# MinieasySens-RFM_V03-Build004.net
KiCad netlist of a schematic drawn in EAGLE
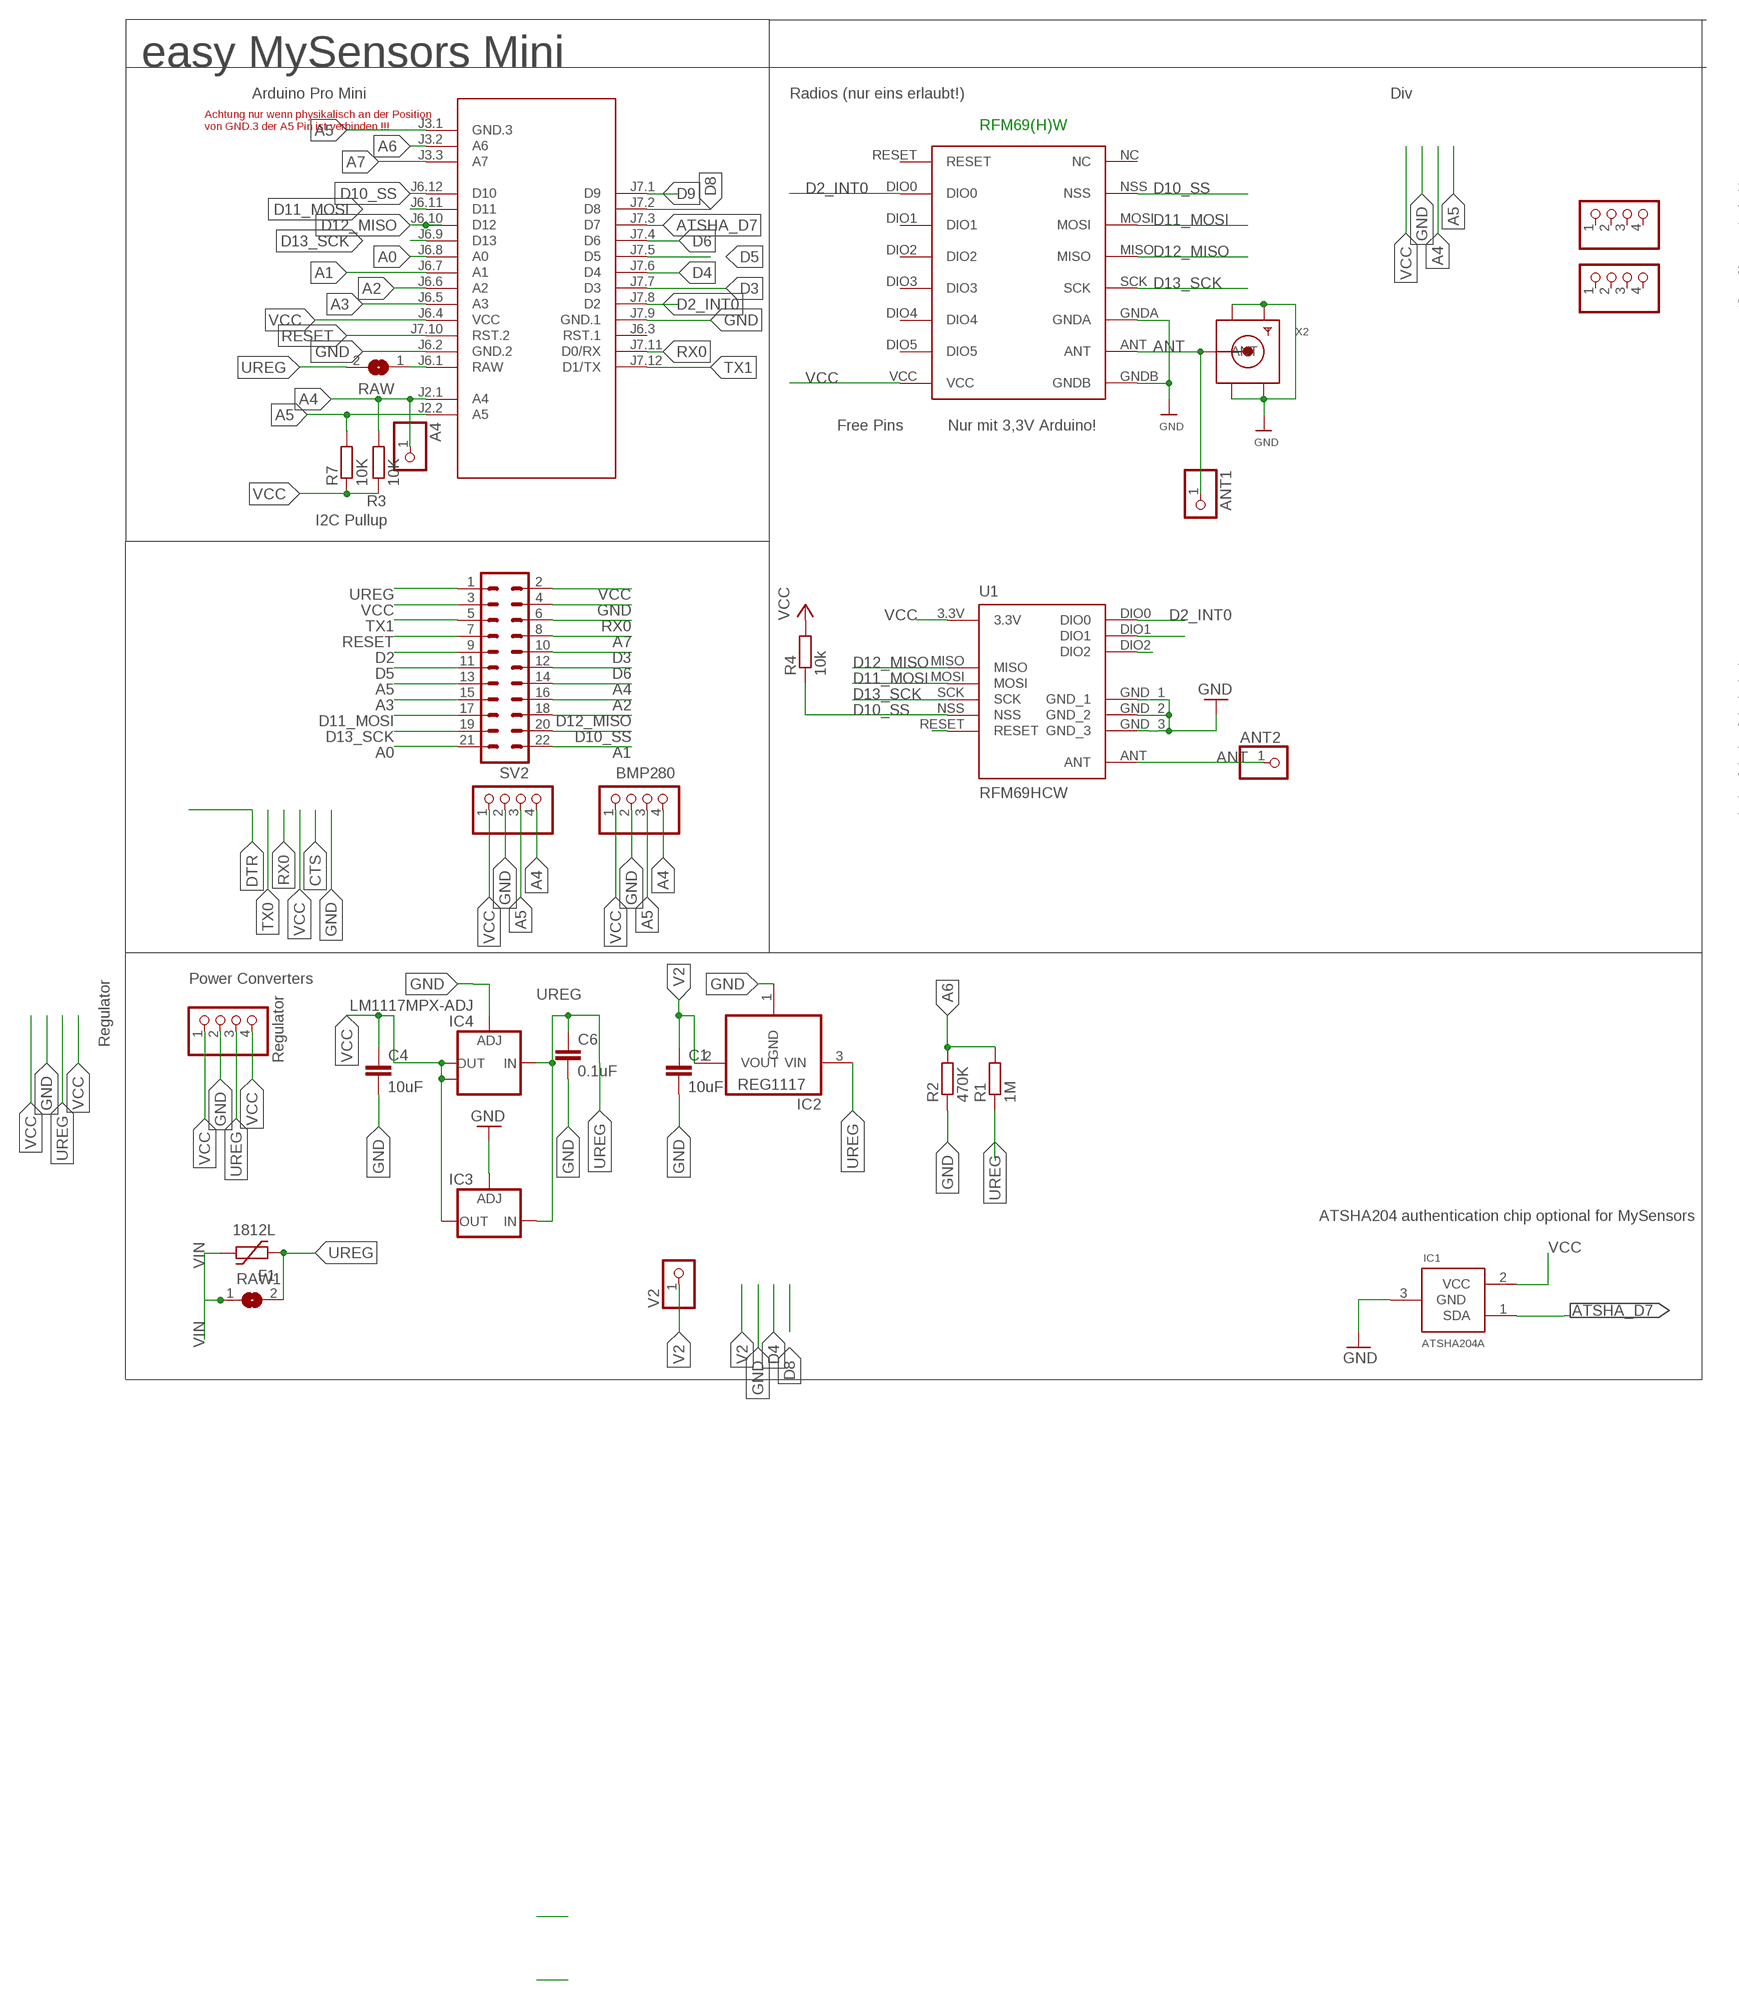
[diagram p0: schematic, sheet 1, part 1 of 2]
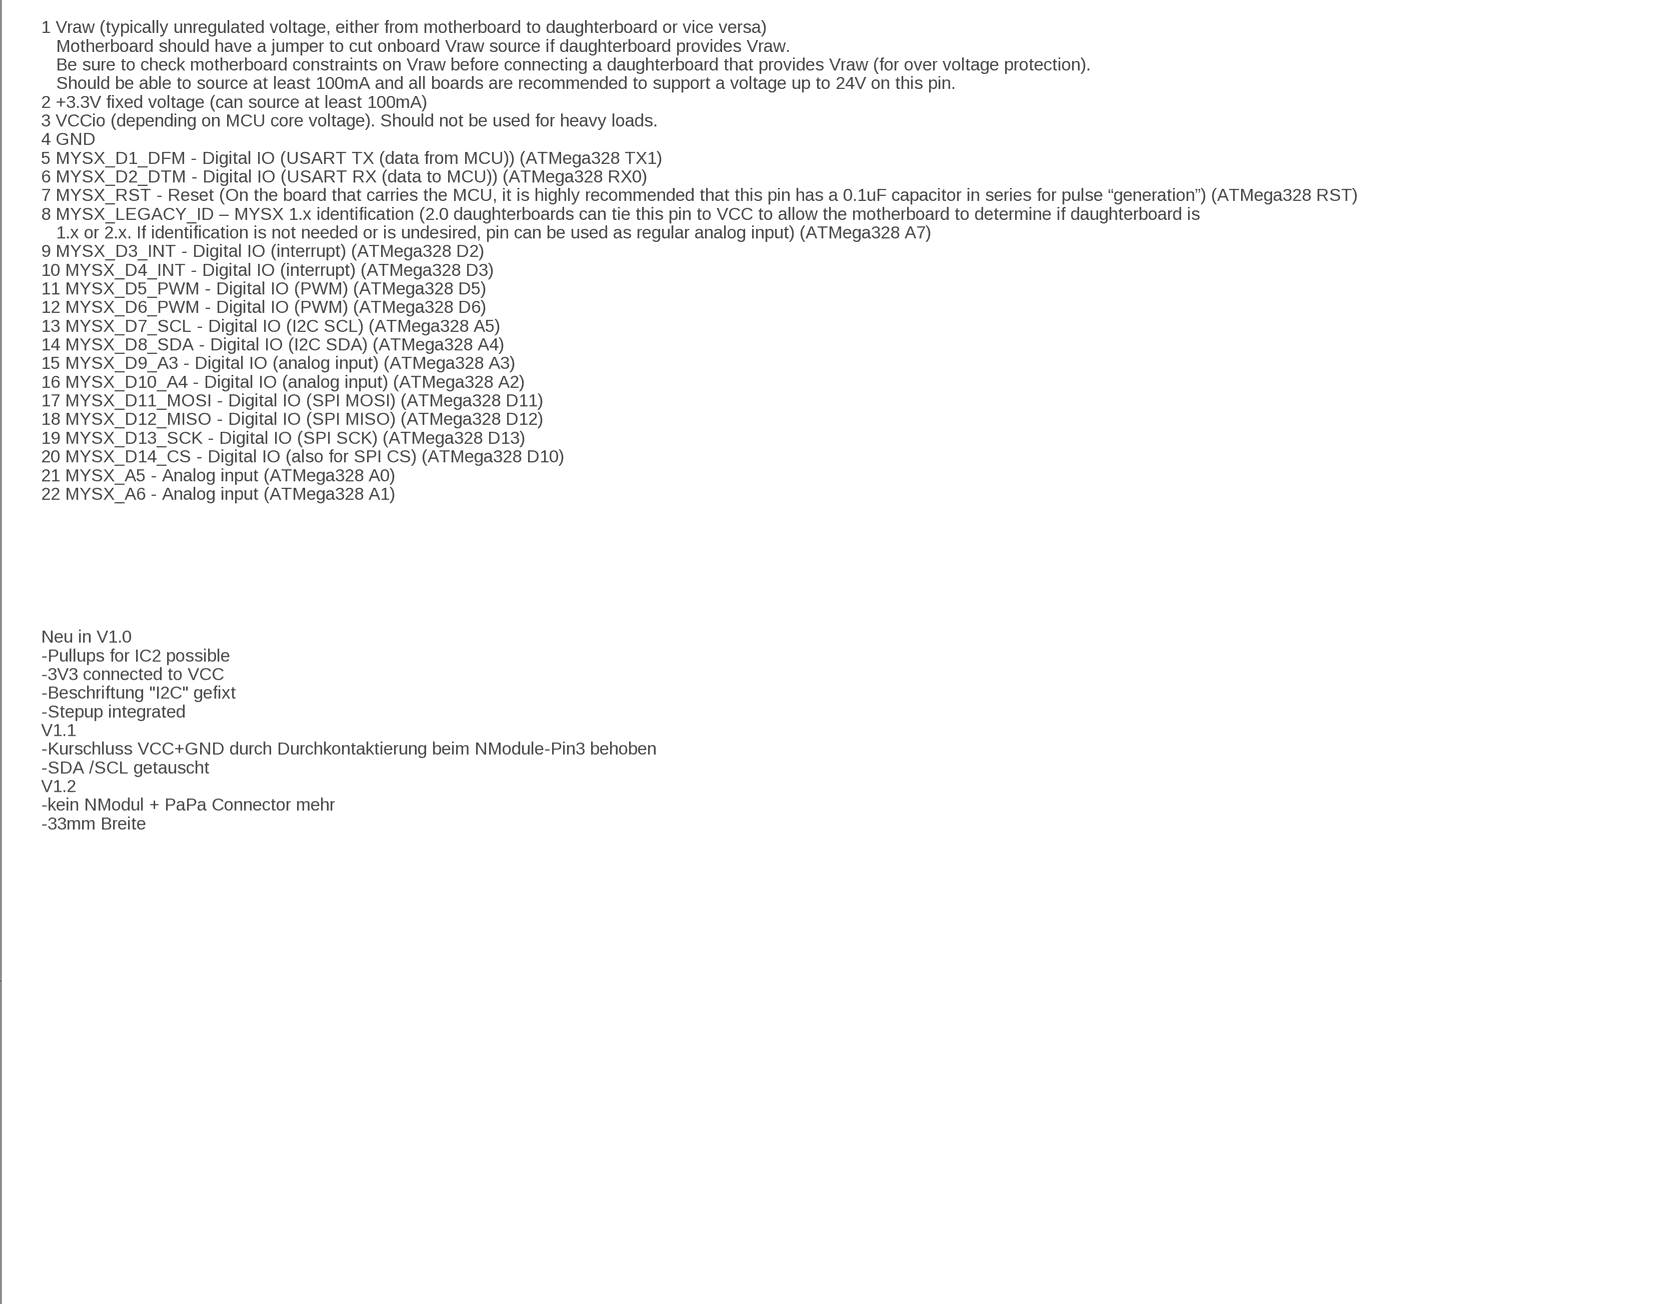
[diagram p1: schematic, sheet 1, part 2 of 2]

(export (version "E")
  (design (tool "Eeschema 10.0.6"))
  (components
    (comp (ref "A4")
      (value "PINHD-1X1")
      (footprint "eagle-import:1X01")
      (libsource (lib "eagle-import") (part "PINHD-1X1"))
    )
    (comp (ref "ANT1")
      (value "PINHD-1X1")
      (footprint "eagle-import:1X01")
      (libsource (lib "eagle-import") (part "PINHD-1X1"))
    )
    (comp (ref "ANT2")
      (value "PINHD-1X1")
      (footprint "eagle-import:1X01")
      (libsource (lib "eagle-import") (part "PINHD-1X1"))
    )
    (comp (ref "BH1750")
      (value "PINHD-1X04_2.54-S")
      (footprint "eagle-import:1X04-S")
      (libsource (lib "eagle-import") (part "PINHD-1X04_2.54-S"))
    )
    (comp (ref "C1")
      (value "10uF")
      (footprint "eagle-import:C1210")
      (libsource (lib "eagle-import") (part "C-EUC1210"))
    )
    (comp (ref "C4")
      (value "10uF")
      (footprint "eagle-import:C1210")
      (libsource (lib "eagle-import") (part "C-EUC1210"))
    )
    (comp (ref "C6")
      (value "0.1uF")
      (footprint "eagle-import:C1206")
      (libsource (lib "eagle-import") (part "C-EUC1206"))
    )
    (comp (ref "F1")
      (value "1812L")
      (footprint "eagle-import:1812L")
      (libsource (lib "eagle-import") (part "1812L"))
    )
    (comp (ref "I2C-1")
      (value "PINHD-1X04_2.54-S")
      (footprint "eagle-import:1X04-S")
      (libsource (lib "eagle-import") (part "PINHD-1X04_2.54-S"))
    )
    (comp (ref "IC1")
      (value "ATSHA204A")
      (footprint "eagle-import:SOT23")
      (libsource (lib "eagle-import") (part "ATSHA204A"))
    )
    (comp (ref "IC2")
      (value "REG1117")
      (footprint "eagle-import:SOT223")
      (libsource (lib "eagle-import") (part "REG1117"))
    )
    (comp (ref "IC3")
      (value "LD117ADT50TR")
      (footprint "eagle-import:DPACK")
      (libsource (lib "eagle-import") (part "LD117A?DT50TR"))
    )
    (comp (ref "IC4")
      (value "LM1117MPX-ADJ")
      (footprint "eagle-import:SOT223")
      (libsource (lib "eagle-import") (part "LM1117MPX-ADJ"))
    )
    (comp (ref "JP1")
      (value "PINHD-1X04_2.54-S")
      (footprint "eagle-import:1X04-S")
      (libsource (lib "eagle-import") (part "PINHD-1X04_2.54-S"))
    )
    (comp (ref "JP2")
      (value "PINHD-1X04_2.54-S")
      (footprint "eagle-import:1X04-S")
      (libsource (lib "eagle-import") (part "PINHD-1X04_2.54-S"))
    )
    (comp (ref "M1")
      (value "ARDUINO-PRO-MINI-3.3V#NP")
      (footprint "eagle-import:ARDUINO-PRO-MINI#NP")
      (libsource (lib "eagle-import") (part "ARDUINO-PRO-MINI-#NP3.3V"))
    )
    (comp (ref "R1")
      (value "1M")
      (footprint "eagle-import:R0805")
      (libsource (lib "eagle-import") (part "R-EU_R0805"))
    )
    (comp (ref "R2")
      (value "470K")
      (footprint "eagle-import:R0805")
      (libsource (lib "eagle-import") (part "R-EU_R0805"))
    )
    (comp (ref "R3")
      (value "10K")
      (footprint "eagle-import:R0805")
      (libsource (lib "eagle-import") (part "R-EU_R0805"))
    )
    (comp (ref "R4")
      (value "10k")
      (footprint "eagle-import:M0805")
      (libsource (lib "eagle-import") (part "R-EU_M0805"))
    )
    (comp (ref "R7")
      (value "10K")
      (footprint "eagle-import:R0805")
      (libsource (lib "eagle-import") (part "R-EU_R0805"))
    )
    (comp (ref "RAW") (value "SJ") (footprint "eagle-import:SJ") (libsource (lib "eagle-import") (part "SJ")))
    (comp (ref "RAW1")
      (value "SJ")
      (footprint "eagle-import:SJ")
      (libsource (lib "eagle-import") (part "SJ"))
    )
    (comp (ref "RFM69W")
      (value "RFM69HW")
      (footprint "eagle-import:RFM")
      (libsource (lib "eagle-import") (part "RFM69HW"))
    )
    (comp (ref "STEPDWN")
      (value "PINHD-1X04_2.54-S")
      (footprint "eagle-import:1X04-S")
      (libsource (lib "eagle-import") (part "PINHD-1X04_2.54-S"))
    )
    (comp (ref "SV2")
      (value "MA11-2")
      (footprint "eagle-import:MA11-2")
      (libsource (lib "eagle-import") (part "MA11-2"))
    )
    (comp (ref "U1")
      (value "RFM69HCW")
      (footprint "eagle-import:RFM69HCW-XXXS2")
      (libsource (lib "eagle-import") (part "RFM69HCW"))
    )
    (comp (ref "V2")
      (value "PINHD-1X1")
      (footprint "eagle-import:1X01")
      (libsource (lib "eagle-import") (part "PINHD-1X1"))
    )
    (comp (ref "X2")
      (value "SMACONNECTOR_EDGE")
      (footprint "eagle-import:SMA_EDGELAUNCH")
      (libsource (lib "eagle-import") (part "SMACONNECTOR_EDGE"))
    )
  )
  (nets
    (net (code "1") (name "/ANT") (class "Default")
      (node (ref "ANT1") (pin "1") (pinfunction "1_1") (pintype "passive"))
      (node (ref "ANT2") (pin "1") (pinfunction "1_1") (pintype "passive"))
      (node (ref "RFM69W") (pin "ANT") (pinfunction "ANT_ANT") (pintype "bidirectional"))
      (node (ref "U1") (pin "ANT") (pinfunction "ANT_ANT") (pintype "passive"))
      (node (ref "X2") (pin "P") (pinfunction "ANT_P") (pintype "bidirectional"))
    )
    (net (code "2") (name "/D2") (class "Default")
      (node (ref "SV2") (pin "9") (pinfunction "9_9") (pintype "passive"))
    )
    (net (code "3") (name "/VIN") (class "Default")
      (node (ref "F1") (pin "P$2") (pinfunction "2_P$2") (pintype "passive"))
      (node (ref "RAW1") (pin "1") (pinfunction "1_1") (pintype "passive"))
    )
    (net (code "4") (name "A0") (class "Default")
      (node (ref "M1") (pin "J6.8") (pinfunction "A0_J6.8") (pintype "bidirectional"))
      (node (ref "SV2") (pin "21") (pinfunction "21_21") (pintype "passive"))
    )
    (net (code "5") (name "A1") (class "Default")
      (node (ref "M1") (pin "J6.7") (pinfunction "A1_J6.7") (pintype "bidirectional"))
      (node (ref "SV2") (pin "22") (pinfunction "22_22") (pintype "passive"))
    )
    (net (code "6") (name "A2") (class "Default")
      (node (ref "M1") (pin "J6.6") (pinfunction "A2_J6.6") (pintype "bidirectional"))
      (node (ref "SV2") (pin "16") (pinfunction "16_16") (pintype "passive"))
    )
    (net (code "7") (name "A3") (class "Default")
      (node (ref "M1") (pin "J6.5") (pinfunction "A3_J6.5") (pintype "bidirectional"))
      (node (ref "SV2") (pin "15") (pinfunction "15_15") (pintype "passive"))
    )
    (net (code "8") (name "A4") (class "Default")
      (node (ref "A4") (pin "1") (pinfunction "1_1") (pintype "passive"))
      (node (ref "BH1750") (pin "4") (pinfunction "4_4") (pintype "passive"))
      (node (ref "I2C-1") (pin "4") (pinfunction "4_4") (pintype "passive"))
      (node (ref "M1") (pin "J2.1") (pinfunction "A4_J2.1") (pintype "bidirectional"))
      (node (ref "R3") (pin "2") (pinfunction "2_2") (pintype "passive"))
      (node (ref "SV2") (pin "14") (pinfunction "14_14") (pintype "passive"))
    )
    (net (code "9") (name "A5") (class "Default")
      (node (ref "BH1750") (pin "3") (pinfunction "3_3") (pintype "passive"))
      (node (ref "I2C-1") (pin "3") (pinfunction "3_3") (pintype "passive"))
      (node (ref "M1") (pin "J2.2") (pinfunction "A5_J2.2") (pintype "bidirectional"))
      (node (ref "M1") (pin "J3.1") (pinfunction "GND.3_J3.1") (pintype "bidirectional"))
      (node (ref "R7") (pin "2") (pinfunction "2_2") (pintype "passive"))
      (node (ref "SV2") (pin "13") (pinfunction "13_13") (pintype "passive"))
    )
    (net (code "10") (name "A6") (class "Default")
      (node (ref "M1") (pin "J3.2") (pinfunction "A6_J3.2") (pintype "bidirectional"))
      (node (ref "R1") (pin "2") (pinfunction "2_2") (pintype "passive"))
      (node (ref "R2") (pin "2") (pinfunction "2_2") (pintype "passive"))
    )
    (net (code "11") (name "A7") (class "Default")
      (node (ref "M1") (pin "J3.3") (pinfunction "A7_J3.3") (pintype "bidirectional"))
      (node (ref "SV2") (pin "8") (pinfunction "8_8") (pintype "passive"))
    )
    (net (code "12") (name "ATSHA_D7") (class "Default")
      (node (ref "IC1") (pin "1") (pinfunction "SDA_1") (pintype "bidirectional"))
      (node (ref "M1") (pin "J7.3") (pinfunction "D7_J7.3") (pintype "bidirectional"))
    )
    (net (code "14") (name "D2_INT0") (class "Default")
      (node (ref "M1") (pin "J7.8") (pinfunction "D2_J7.8") (pintype "bidirectional"))
      (node (ref "RFM69W") (pin "DIO0") (pinfunction "DIO0_DIO0") (pintype "bidirectional"))
      (node (ref "U1") (pin "DIO0") (pinfunction "DIO0_DIO0") (pintype "bidirectional"))
    )
    (net (code "15") (name "D3") (class "Default")
      (node (ref "M1") (pin "J7.7") (pinfunction "D3_J7.7") (pintype "bidirectional"))
      (node (ref "SV2") (pin "10") (pinfunction "10_10") (pintype "passive"))
    )
    (net (code "16") (name "D4") (class "Default")
      (node (ref "M1") (pin "J7.6") (pinfunction "D4_J7.6") (pintype "bidirectional"))
    )
    (net (code "17") (name "D5") (class "Default")
      (node (ref "M1") (pin "J7.5") (pinfunction "D5_J7.5") (pintype "bidirectional"))
      (node (ref "SV2") (pin "11") (pinfunction "11_11") (pintype "passive"))
    )
    (net (code "18") (name "D6") (class "Default")
      (node (ref "M1") (pin "J7.4") (pinfunction "D6_J7.4") (pintype "bidirectional"))
      (node (ref "SV2") (pin "12") (pinfunction "12_12") (pintype "passive"))
    )
    (net (code "19") (name "D8") (class "Default")
      (node (ref "M1") (pin "J7.2") (pinfunction "D8_J7.2") (pintype "bidirectional"))
    )
    (net (code "20") (name "D9") (class "Default")
      (node (ref "M1") (pin "J7.1") (pinfunction "D9_J7.1") (pintype "bidirectional"))
    )
    (net (code "21") (name "D10_SS") (class "Default")
      (node (ref "M1") (pin "J6.12") (pinfunction "D10_J6.12") (pintype "bidirectional"))
      (node (ref "R4") (pin "1") (pinfunction "1_1") (pintype "passive"))
      (node (ref "RFM69W") (pin "NSS") (pinfunction "NSS_NSS") (pintype "bidirectional"))
      (node (ref "SV2") (pin "20") (pinfunction "20_20") (pintype "passive"))
      (node (ref "U1") (pin "NSS") (pinfunction "NSS_NSS") (pintype "input"))
    )
    (net (code "22") (name "D11_MOSI") (class "Default")
      (node (ref "M1") (pin "J6.11") (pinfunction "D11_J6.11") (pintype "bidirectional"))
      (node (ref "RFM69W") (pin "MOSI") (pinfunction "MOSI_MOSI") (pintype "bidirectional"))
      (node (ref "SV2") (pin "17") (pinfunction "17_17") (pintype "passive"))
      (node (ref "U1") (pin "MOSI") (pinfunction "MOSI_MOSI") (pintype "input"))
    )
    (net (code "23") (name "D12_MISO") (class "Default")
      (node (ref "M1") (pin "J6.10") (pinfunction "D12_J6.10") (pintype "bidirectional"))
      (node (ref "RFM69W") (pin "MISO") (pinfunction "MISO_MISO") (pintype "bidirectional"))
      (node (ref "SV2") (pin "18") (pinfunction "18_18") (pintype "passive"))
      (node (ref "U1") (pin "MISO") (pinfunction "MISO_MISO") (pintype "bidirectional"))
    )
    (net (code "24") (name "D13_SCK") (class "Default")
      (node (ref "M1") (pin "J6.9") (pinfunction "D13_J6.9") (pintype "bidirectional"))
      (node (ref "RFM69W") (pin "SCK") (pinfunction "SCK_SCK") (pintype "bidirectional"))
      (node (ref "SV2") (pin "19") (pinfunction "19_19") (pintype "passive"))
      (node (ref "U1") (pin "SCK") (pinfunction "SCK_SCK") (pintype "input"))
    )
    (net (code "26") (name "GND") (class "Default")
      (node (ref "BH1750") (pin "2") (pinfunction "2_2") (pintype "passive"))
      (node (ref "C1") (pin "2") (pinfunction "2_2") (pintype "passive"))
      (node (ref "C4") (pin "2") (pinfunction "2_2") (pintype "passive"))
      (node (ref "C6") (pin "2") (pinfunction "2_2") (pintype "passive"))
      (node (ref "I2C-1") (pin "2") (pinfunction "2_2") (pintype "passive"))
      (node (ref "IC1") (pin "3") (pinfunction "GND_3") (pintype "bidirectional"))
      (node (ref "IC2") (pin "1") (pinfunction "GND_1") (pintype "power_in"))
      (node (ref "IC3") (pin "1") (pinfunction "ADJ_1") (pintype "input"))
      (node (ref "IC4") (pin "1") (pinfunction "ADJ_1") (pintype "input"))
      (node (ref "M1") (pin "J6.2") (pinfunction "GND.2_J6.2") (pintype "power_in"))
      (node (ref "M1") (pin "J7.9") (pinfunction "GND.1_J7.9") (pintype "power_in"))
      (node (ref "R2") (pin "1") (pinfunction "1_1") (pintype "passive"))
      (node (ref "RFM69W") (pin "GNDA") (pinfunction "GNDA_GNDA") (pintype "bidirectional"))
      (node (ref "RFM69W") (pin "GNDB") (pinfunction "GNDB_GNDB") (pintype "bidirectional"))
      (node (ref "STEPDWN") (pin "2") (pinfunction "2_2") (pintype "passive"))
      (node (ref "SV2") (pin "4") (pinfunction "4_4") (pintype "passive"))
      (node (ref "U1") (pin "GND_1") (pinfunction "GND_1_GND_1") (pintype "power_in"))
      (node (ref "U1") (pin "GND_2") (pinfunction "GND_2_GND_2") (pintype "power_in"))
      (node (ref "U1") (pin "GND_3") (pinfunction "GND_3_GND_3") (pintype "power_in"))
      (node (ref "X2") (pin "GND@1") (pinfunction "GND4_GND@1") (pintype "power_in"))
      (node (ref "X2") (pin "GND@2") (pinfunction "GND3_GND@2") (pintype "power_in"))
      (node (ref "X2") (pin "GND@3") (pinfunction "GND2_GND@3") (pintype "power_in"))
      (node (ref "X2") (pin "GND@4") (pinfunction "GND1_GND@4") (pintype "power_in"))
    )
    (net (code "27") (name "Net-(M1-RAW)") (class "Default")
      (node (ref "M1") (pin "J6.1") (pinfunction "RAW_J6.1") (pintype "power_in"))
      (node (ref "RAW") (pin "1") (pinfunction "1_1") (pintype "passive"))
    )
    (net (code "28") (name "RESET") (class "Default")
      (node (ref "M1") (pin "J7.10") (pinfunction "RST.2_J7.10") (pintype "bidirectional"))
      (node (ref "SV2") (pin "7") (pinfunction "7_7") (pintype "passive"))
    )
    (net (code "29") (name "RX0") (class "Default")
      (node (ref "M1") (pin "J7.11") (pinfunction "D0/RX_J7.11") (pintype "bidirectional"))
      (node (ref "SV2") (pin "6") (pinfunction "6_6") (pintype "passive"))
    )
    (net (code "31") (name "TX1") (class "Default")
      (node (ref "M1") (pin "J7.12") (pinfunction "D1/TX_J7.12") (pintype "bidirectional"))
      (node (ref "SV2") (pin "5") (pinfunction "5_5") (pintype "passive"))
    )
    (net (code "32") (name "UREG") (class "Default")
      (node (ref "C6") (pin "1") (pinfunction "1_1") (pintype "passive"))
      (node (ref "F1") (pin "P$1") (pinfunction "1_P$1") (pintype "passive"))
      (node (ref "IC2") (pin "3") (pinfunction "VIN_3") (pintype "input"))
      (node (ref "IC3") (pin "3") (pinfunction "IN_3") (pintype "input"))
      (node (ref "IC4") (pin "3") (pinfunction "IN_3") (pintype "input"))
      (node (ref "R1") (pin "1") (pinfunction "1_1") (pintype "passive"))
      (node (ref "RAW") (pin "2") (pinfunction "2_2") (pintype "passive"))
      (node (ref "RAW1") (pin "2") (pinfunction "2_2") (pintype "passive"))
      (node (ref "STEPDWN") (pin "3") (pinfunction "3_3") (pintype "passive"))
      (node (ref "SV2") (pin "1") (pinfunction "1_1") (pintype "passive"))
    )
    (net (code "33") (name "V2") (class "Default")
      (node (ref "C1") (pin "1") (pinfunction "1_1") (pintype "passive"))
      (node (ref "IC2") (pin "2") (pinfunction "VOUT_2") (pintype "output"))
      (node (ref "V2") (pin "1") (pinfunction "1_1") (pintype "passive"))
    )
    (net (code "34") (name "VCC") (class "Default")
      (node (ref "BH1750") (pin "1") (pinfunction "1_1") (pintype "passive"))
      (node (ref "C4") (pin "1") (pinfunction "1_1") (pintype "passive"))
      (node (ref "I2C-1") (pin "1") (pinfunction "1_1") (pintype "passive"))
      (node (ref "IC1") (pin "2") (pinfunction "VCC_2") (pintype "bidirectional"))
      (node (ref "IC3") (pin "4") (pinfunction "OUT_4") (pintype "passive"))
      (node (ref "IC4") (pin "2") (pinfunction "OUT_2") (pintype "passive"))
      (node (ref "IC4") (pin "TAB") (pinfunction "OUT1_TAB") (pintype "passive"))
      (node (ref "M1") (pin "J6.4") (pinfunction "VCC_J6.4") (pintype "power_in"))
      (node (ref "R3") (pin "1") (pinfunction "1_1") (pintype "passive"))
      (node (ref "R4") (pin "2") (pinfunction "2_2") (pintype "passive"))
      (node (ref "R7") (pin "1") (pinfunction "1_1") (pintype "passive"))
      (node (ref "RFM69W") (pin "VCC") (pinfunction "VCC_VCC") (pintype "bidirectional"))
      (node (ref "STEPDWN") (pin "1") (pinfunction "1_1") (pintype "passive"))
      (node (ref "STEPDWN") (pin "4") (pinfunction "4_4") (pintype "passive"))
      (node (ref "SV2") (pin "2") (pinfunction "2_2") (pintype "passive"))
      (node (ref "SV2") (pin "3") (pinfunction "3_3") (pintype "passive"))
      (node (ref "U1") (pin "3.3V") (pinfunction "3.3V_3.3V") (pintype "power_in"))
    )
    (net (code "35") (name "unconnected-(JP1-Pad1)") (class "Default")
      (node (ref "JP1") (pin "1") (pinfunction "1_1") (pintype "passive"))
    )
    (net (code "36") (name "unconnected-(JP1-Pad2)") (class "Default")
      (node (ref "JP1") (pin "2") (pinfunction "2_2") (pintype "passive"))
    )
    (net (code "37") (name "unconnected-(JP1-Pad3)") (class "Default")
      (node (ref "JP1") (pin "3") (pinfunction "3_3") (pintype "passive"))
    )
    (net (code "38") (name "unconnected-(JP1-Pad4)") (class "Default")
      (node (ref "JP1") (pin "4") (pinfunction "4_4") (pintype "passive"))
    )
    (net (code "39") (name "unconnected-(JP2-Pad1)") (class "Default")
      (node (ref "JP2") (pin "1") (pinfunction "1_1") (pintype "passive"))
    )
    (net (code "40") (name "unconnected-(JP2-Pad2)") (class "Default")
      (node (ref "JP2") (pin "2") (pinfunction "2_2") (pintype "passive"))
    )
    (net (code "41") (name "unconnected-(JP2-Pad3)") (class "Default")
      (node (ref "JP2") (pin "3") (pinfunction "3_3") (pintype "passive"))
    )
    (net (code "42") (name "unconnected-(JP2-Pad4)") (class "Default")
      (node (ref "JP2") (pin "4") (pinfunction "4_4") (pintype "passive"))
    )
    (net (code "43") (name "unconnected-(M1-RST.1-PadJ6.3)") (class "Default")
      (node (ref "M1") (pin "J6.3") (pinfunction "RST.1_J6.3") (pintype "bidirectional"))
    )
    (net (code "44") (name "unconnected-(RFM69W-PadDIO1)") (class "Default")
      (node (ref "RFM69W") (pin "DIO1") (pinfunction "DIO1_DIO1") (pintype "bidirectional"))
    )
    (net (code "45") (name "unconnected-(RFM69W-PadDIO2)") (class "Default")
      (node (ref "RFM69W") (pin "DIO2") (pinfunction "DIO2_DIO2") (pintype "bidirectional"))
    )
    (net (code "46") (name "unconnected-(RFM69W-PadDIO3)") (class "Default")
      (node (ref "RFM69W") (pin "DIO3") (pinfunction "DIO3_DIO3") (pintype "bidirectional"))
    )
    (net (code "47") (name "unconnected-(RFM69W-PadDIO4)") (class "Default")
      (node (ref "RFM69W") (pin "DIO4") (pinfunction "DIO4_DIO4") (pintype "bidirectional"))
    )
    (net (code "48") (name "unconnected-(RFM69W-PadDIO5)") (class "Default")
      (node (ref "RFM69W") (pin "DIO5") (pinfunction "DIO5_DIO5") (pintype "bidirectional"))
    )
    (net (code "49") (name "unconnected-(RFM69W-PadNC)") (class "Default")
      (node (ref "RFM69W") (pin "NC") (pinfunction "NC_NC") (pintype "bidirectional"))
    )
    (net (code "50") (name "unconnected-(RFM69W-PadRESET)") (class "Default")
      (node (ref "RFM69W") (pin "RESET") (pinfunction "RESET_RESET") (pintype "bidirectional"))
    )
    (net (code "51") (name "unconnected-(U1-PadDIO1)") (class "Default")
      (node (ref "U1") (pin "DIO1") (pinfunction "DIO1_DIO1") (pintype "bidirectional"))
    )
    (net (code "52") (name "unconnected-(U1-PadDIO2)") (class "Default")
      (node (ref "U1") (pin "DIO2") (pinfunction "DIO2_DIO2") (pintype "bidirectional"))
    )
    (net (code "53") (name "unconnected-(U1-PadRESET)") (class "Default")
      (node (ref "U1") (pin "RESET") (pinfunction "RESET_RESET") (pintype "input"))
    )
  )
)
